# OSSC_HDMI_Audio_v1_5_A4b.net
KiCad netlist of a schematic drawn in EAGLE
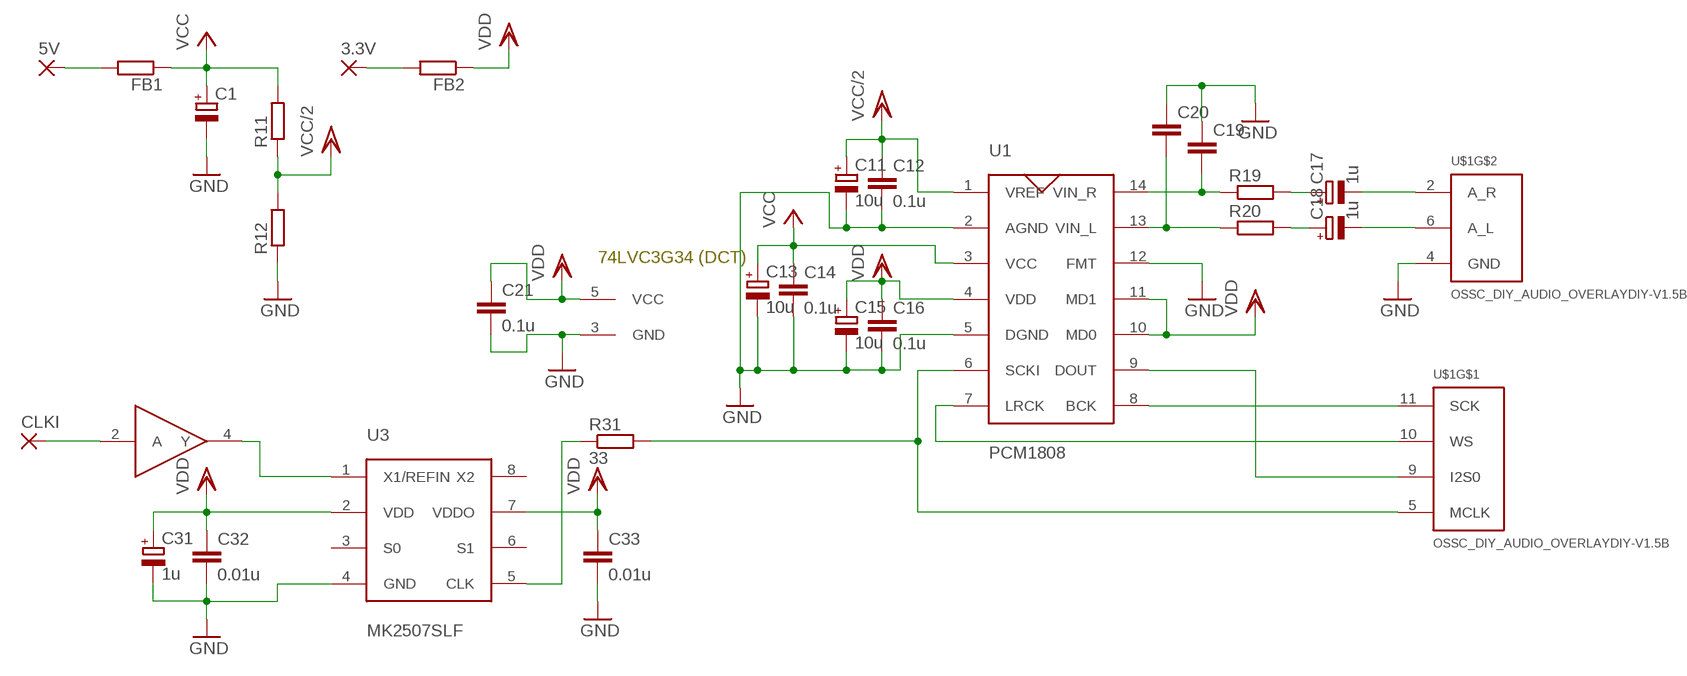
[diagram p0: schematic, sheet 1]

(export (version "E")
  (design (tool "Eeschema 10.0.6"))
  (components
    (comp (ref "3.3V")
      (value "SMD2")
      (footprint "eagle-import:SMD1,27-2,54")
      (libsource (lib "eagle-import") (part "SMD2"))
    )
    (comp (ref "5V")
      (value "SMD2")
      (footprint "eagle-import:SMD1,27-2,54")
      (libsource (lib "eagle-import") (part "SMD2"))
    )
    (comp (ref "C1")
      (value "CPOL-EUSMCC")
      (footprint "eagle-import:SMC_C")
      (libsource (lib "eagle-import") (part "CPOL-EUSMCC"))
    )
    (comp (ref "C11")
      (value "10u")
      (footprint "eagle-import:SMC_A")
      (libsource (lib "eagle-import") (part "CPOL-EUSMCA"))
    )
    (comp (ref "C12")
      (value "0.1u")
      (footprint "eagle-import:C0603")
      (libsource (lib "eagle-import") (part "C-EUC0603"))
    )
    (comp (ref "C13")
      (value "10u")
      (footprint "eagle-import:SMC_A")
      (libsource (lib "eagle-import") (part "CPOL-EUSMCA"))
    )
    (comp (ref "C14")
      (value "0.1u")
      (footprint "eagle-import:C0603")
      (libsource (lib "eagle-import") (part "C-EUC0603"))
    )
    (comp (ref "C15")
      (value "10u")
      (footprint "eagle-import:SMC_A")
      (libsource (lib "eagle-import") (part "CPOL-EUSMCA"))
    )
    (comp (ref "C16")
      (value "0.1u")
      (footprint "eagle-import:C0603")
      (libsource (lib "eagle-import") (part "C-EUC0603"))
    )
    (comp (ref "C17")
      (value "1u")
      (footprint "eagle-import:SMC_A")
      (libsource (lib "eagle-import") (part "CPOL-EUSMCA"))
    )
    (comp (ref "C18")
      (value "1u")
      (footprint "eagle-import:SMC_A")
      (libsource (lib "eagle-import") (part "CPOL-EUSMCA"))
    )
    (comp (ref "C19")
      (value "C-EUC0603")
      (footprint "eagle-import:C0603")
      (libsource (lib "eagle-import") (part "C-EUC0603"))
    )
    (comp (ref "C20")
      (value "C-EUC0603")
      (footprint "eagle-import:C0603")
      (libsource (lib "eagle-import") (part "C-EUC0603"))
    )
    (comp (ref "C21")
      (value "0.1u")
      (footprint "eagle-import:C0603")
      (libsource (lib "eagle-import") (part "C-EUC0603"))
    )
    (comp (ref "C31")
      (value "1u")
      (footprint "eagle-import:SMC_A")
      (libsource (lib "eagle-import") (part "CPOL-EUSMCA"))
    )
    (comp (ref "C32")
      (value "0.01u")
      (footprint "eagle-import:C0603")
      (libsource (lib "eagle-import") (part "C-EUC0603"))
    )
    (comp (ref "C33")
      (value "0.01u")
      (footprint "eagle-import:C0603")
      (libsource (lib "eagle-import") (part "C-EUC0603"))
    )
    (comp (ref "CLKI")
      (value "SMD2")
      (footprint "eagle-import:SMD1,27-2,54")
      (libsource (lib "eagle-import") (part "SMD2"))
    )
    (comp (ref "FB1")
      (value "R-EU_R0603")
      (footprint "eagle-import:R0603")
      (libsource (lib "eagle-import") (part "R-EU_R0603"))
    )
    (comp (ref "FB2")
      (value "R-EU_R0603")
      (footprint "eagle-import:R0603")
      (libsource (lib "eagle-import") (part "R-EU_R0603"))
    )
    (comp (ref "R11")
      (value "R-EU_R0603")
      (footprint "eagle-import:R0603")
      (libsource (lib "eagle-import") (part "R-EU_R0603"))
    )
    (comp (ref "R12")
      (value "R-EU_R0603")
      (footprint "eagle-import:R0603")
      (libsource (lib "eagle-import") (part "R-EU_R0603"))
    )
    (comp (ref "R19")
      (value "R-EU_R0603")
      (footprint "eagle-import:R0603")
      (libsource (lib "eagle-import") (part "R-EU_R0603"))
    )
    (comp (ref "R20")
      (value "R-EU_R0603")
      (footprint "eagle-import:R0603")
      (libsource (lib "eagle-import") (part "R-EU_R0603"))
    )
    (comp (ref "R31")
      (value "33")
      (footprint "eagle-import:R0603")
      (libsource (lib "eagle-import") (part "R-EU_R0603"))
    )
    (comp (ref "U$1")
      (value "OSSC_DIY_AUDIO_OVERLAYDIY-V1.5B")
      (footprint "eagle-import:OSSC_OVERLAY_V1.5B")
      (libsource (lib "eagle-import") (part "OSSC_DIY_AUDIO_OVERLAYDIY-V1.5B"))
    )
    (comp (ref "U1")
      (value "PCM1808")
      (footprint "eagle-import:PCM1808")
      (libsource (lib "eagle-import") (part "PCM1808"))
    )
    (comp (ref "U2")
      (value "74LVC1G34")
      (footprint "eagle-import:74LVC1G34DCK")
      (libsource (lib "eagle-import") (part "74LVC1G34"))
    )
    (comp (ref "U3")
      (value "MK2507SLF")
      (footprint "eagle-import:SOIC8")
      (libsource (lib "eagle-import") (part "MK2507SLF"))
    )
  )
  (nets
    (net (code "1") (name "GND") (class "Default")
      (node (ref "C1") (pin "-") (pinfunction "-_-") (pintype "passive"))
      (node (ref "C11") (pin "-") (pinfunction "-_-") (pintype "passive"))
      (node (ref "C12") (pin "2") (pinfunction "2_2") (pintype "passive"))
      (node (ref "C13") (pin "-") (pinfunction "-_-") (pintype "passive"))
      (node (ref "C14") (pin "2") (pinfunction "2_2") (pintype "passive"))
      (node (ref "C15") (pin "-") (pinfunction "-_-") (pintype "passive"))
      (node (ref "C16") (pin "2") (pinfunction "2_2") (pintype "passive"))
      (node (ref "C19") (pin "1") (pinfunction "1_1") (pintype "passive"))
      (node (ref "C20") (pin "1") (pinfunction "1_1") (pintype "passive"))
      (node (ref "C21") (pin "2") (pinfunction "2_2") (pintype "passive"))
      (node (ref "C31") (pin "-") (pinfunction "-_-") (pintype "passive"))
      (node (ref "C32") (pin "2") (pinfunction "2_2") (pintype "passive"))
      (node (ref "C33") (pin "2") (pinfunction "2_2") (pintype "passive"))
      (node (ref "R12") (pin "1") (pinfunction "1_1") (pintype "passive"))
      (node (ref "U$1") (pin "4") (pinfunction "GND_4") (pintype "bidirectional"))
      (node (ref "U1") (pin "12") (pinfunction "FMT_12") (pintype "bidirectional"))
      (node (ref "U1") (pin "2") (pinfunction "AGND_2") (pintype "bidirectional"))
      (node (ref "U1") (pin "5") (pinfunction "DGND_5") (pintype "bidirectional"))
      (node (ref "U2") (pin "3") (pinfunction "GND_3") (pintype "bidirectional"))
      (node (ref "U3") (pin "4") (pinfunction "GND_4") (pintype "bidirectional"))
    )
    (net (code "2") (name "Net-(3.3V-P)") (class "Default")
      (node (ref "3.3V") (pin "1") (pinfunction "P_1") (pintype "passive"))
      (node (ref "FB2") (pin "2") (pinfunction "2_2") (pintype "passive"))
    )
    (net (code "3") (name "Net-(5V-P)") (class "Default")
      (node (ref "5V") (pin "1") (pinfunction "P_1") (pintype "passive"))
      (node (ref "FB1") (pin "2") (pinfunction "2_2") (pintype "passive"))
    )
    (net (code "4") (name "Net-(C17-Pad+)") (class "Default")
      (node (ref "C17") (pin "+") (pinfunction "+_+") (pintype "passive"))
      (node (ref "R19") (pin "2") (pinfunction "2_2") (pintype "passive"))
    )
    (net (code "5") (name "Net-(C18-Pad+)") (class "Default")
      (node (ref "C18") (pin "+") (pinfunction "+_+") (pintype "passive"))
      (node (ref "R20") (pin "2") (pinfunction "2_2") (pintype "passive"))
    )
    (net (code "6") (name "Net-(CLKI-P)") (class "Default")
      (node (ref "CLKI") (pin "1") (pinfunction "P_1") (pintype "passive"))
      (node (ref "U2") (pin "2") (pinfunction "A_2") (pintype "bidirectional"))
    )
    (net (code "7") (name "Net-(U$1A-I2S0)") (class "Default")
      (node (ref "U$1") (pin "9") (pinfunction "I2S0_9") (pintype "bidirectional"))
      (node (ref "U1") (pin "9") (pinfunction "DOUT_9") (pintype "bidirectional"))
    )
    (net (code "8") (name "Net-(U$1A-MCLK)") (class "Default")
      (node (ref "R31") (pin "2") (pinfunction "2_2") (pintype "passive"))
      (node (ref "U$1") (pin "5") (pinfunction "MCLK_5") (pintype "bidirectional"))
      (node (ref "U1") (pin "6") (pinfunction "SCKI_6") (pintype "bidirectional"))
    )
    (net (code "9") (name "Net-(U$1A-SCK)") (class "Default")
      (node (ref "U$1") (pin "11") (pinfunction "SCK_11") (pintype "bidirectional"))
      (node (ref "U1") (pin "8") (pinfunction "BCK_8") (pintype "bidirectional"))
    )
    (net (code "10") (name "Net-(U$1A-WS)") (class "Default")
      (node (ref "U$1") (pin "10") (pinfunction "WS_10") (pintype "bidirectional"))
      (node (ref "U1") (pin "7") (pinfunction "LRCK_7") (pintype "bidirectional"))
    )
    (net (code "11") (name "Net-(U$1B-A_L)") (class "Default")
      (node (ref "C18") (pin "-") (pinfunction "-_-") (pintype "passive"))
      (node (ref "U$1") (pin "6") (pinfunction "A_L_6") (pintype "bidirectional"))
    )
    (net (code "12") (name "Net-(U$1B-A_R)") (class "Default")
      (node (ref "C17") (pin "-") (pinfunction "-_-") (pintype "passive"))
      (node (ref "U$1") (pin "2") (pinfunction "A_R_2") (pintype "bidirectional"))
    )
    (net (code "13") (name "Net-(U1-VIN_L)") (class "Default")
      (node (ref "C20") (pin "2") (pinfunction "2_2") (pintype "passive"))
      (node (ref "R20") (pin "1") (pinfunction "1_1") (pintype "passive"))
      (node (ref "U1") (pin "13") (pinfunction "VIN_L_13") (pintype "bidirectional"))
    )
    (net (code "14") (name "Net-(U1-VIN_R)") (class "Default")
      (node (ref "C19") (pin "2") (pinfunction "2_2") (pintype "passive"))
      (node (ref "R19") (pin "1") (pinfunction "1_1") (pintype "passive"))
      (node (ref "U1") (pin "14") (pinfunction "VIN_R_14") (pintype "bidirectional"))
    )
    (net (code "15") (name "Net-(U2A-Y)") (class "Default")
      (node (ref "U2") (pin "4") (pinfunction "Y_4") (pintype "bidirectional"))
      (node (ref "U3") (pin "1") (pinfunction "X1/REFIN_1") (pintype "bidirectional"))
    )
    (net (code "16") (name "Net-(U3-CLK)") (class "Default")
      (node (ref "R31") (pin "1") (pinfunction "1_1") (pintype "passive"))
      (node (ref "U3") (pin "5") (pinfunction "CLK_5") (pintype "bidirectional"))
    )
    (net (code "17") (name "VCC") (class "Default")
      (node (ref "C1") (pin "+") (pinfunction "+_+") (pintype "passive"))
      (node (ref "C13") (pin "+") (pinfunction "+_+") (pintype "passive"))
      (node (ref "C14") (pin "1") (pinfunction "1_1") (pintype "passive"))
      (node (ref "FB1") (pin "1") (pinfunction "1_1") (pintype "passive"))
      (node (ref "R11") (pin "2") (pinfunction "2_2") (pintype "passive"))
      (node (ref "U1") (pin "3") (pinfunction "VCC_3") (pintype "bidirectional"))
    )
    (net (code "18") (name "VCC{slash}2") (class "Default")
      (node (ref "C11") (pin "+") (pinfunction "+_+") (pintype "passive"))
      (node (ref "C12") (pin "1") (pinfunction "1_1") (pintype "passive"))
      (node (ref "R11") (pin "1") (pinfunction "1_1") (pintype "passive"))
      (node (ref "R12") (pin "2") (pinfunction "2_2") (pintype "passive"))
      (node (ref "U1") (pin "1") (pinfunction "VREF_1") (pintype "bidirectional"))
    )
    (net (code "19") (name "VDD") (class "Default")
      (node (ref "C15") (pin "+") (pinfunction "+_+") (pintype "passive"))
      (node (ref "C16") (pin "1") (pinfunction "1_1") (pintype "passive"))
      (node (ref "C21") (pin "1") (pinfunction "1_1") (pintype "passive"))
      (node (ref "C31") (pin "+") (pinfunction "+_+") (pintype "passive"))
      (node (ref "C32") (pin "1") (pinfunction "1_1") (pintype "passive"))
      (node (ref "C33") (pin "1") (pinfunction "1_1") (pintype "passive"))
      (node (ref "FB2") (pin "1") (pinfunction "1_1") (pintype "passive"))
      (node (ref "U1") (pin "10") (pinfunction "MD0_10") (pintype "bidirectional"))
      (node (ref "U1") (pin "11") (pinfunction "MD1_11") (pintype "bidirectional"))
      (node (ref "U1") (pin "4") (pinfunction "VDD_4") (pintype "bidirectional"))
      (node (ref "U2") (pin "5") (pinfunction "VCC_5") (pintype "bidirectional"))
      (node (ref "U3") (pin "2") (pinfunction "VDD_2") (pintype "bidirectional"))
      (node (ref "U3") (pin "7") (pinfunction "VDDO_7") (pintype "bidirectional"))
    )
    (net (code "20") (name "unconnected-(U3-S0-Pad3)") (class "Default")
      (node (ref "U3") (pin "3") (pinfunction "S0_3") (pintype "bidirectional"))
    )
    (net (code "21") (name "unconnected-(U3-S1-Pad6)") (class "Default")
      (node (ref "U3") (pin "6") (pinfunction "S1_6") (pintype "bidirectional"))
    )
    (net (code "22") (name "unconnected-(U3-X2-Pad8)") (class "Default")
      (node (ref "U3") (pin "8") (pinfunction "X2_8") (pintype "bidirectional"))
    )
  )
)
